# Power_supply.net
KiCad netlist of a schematic drawn in EAGLE
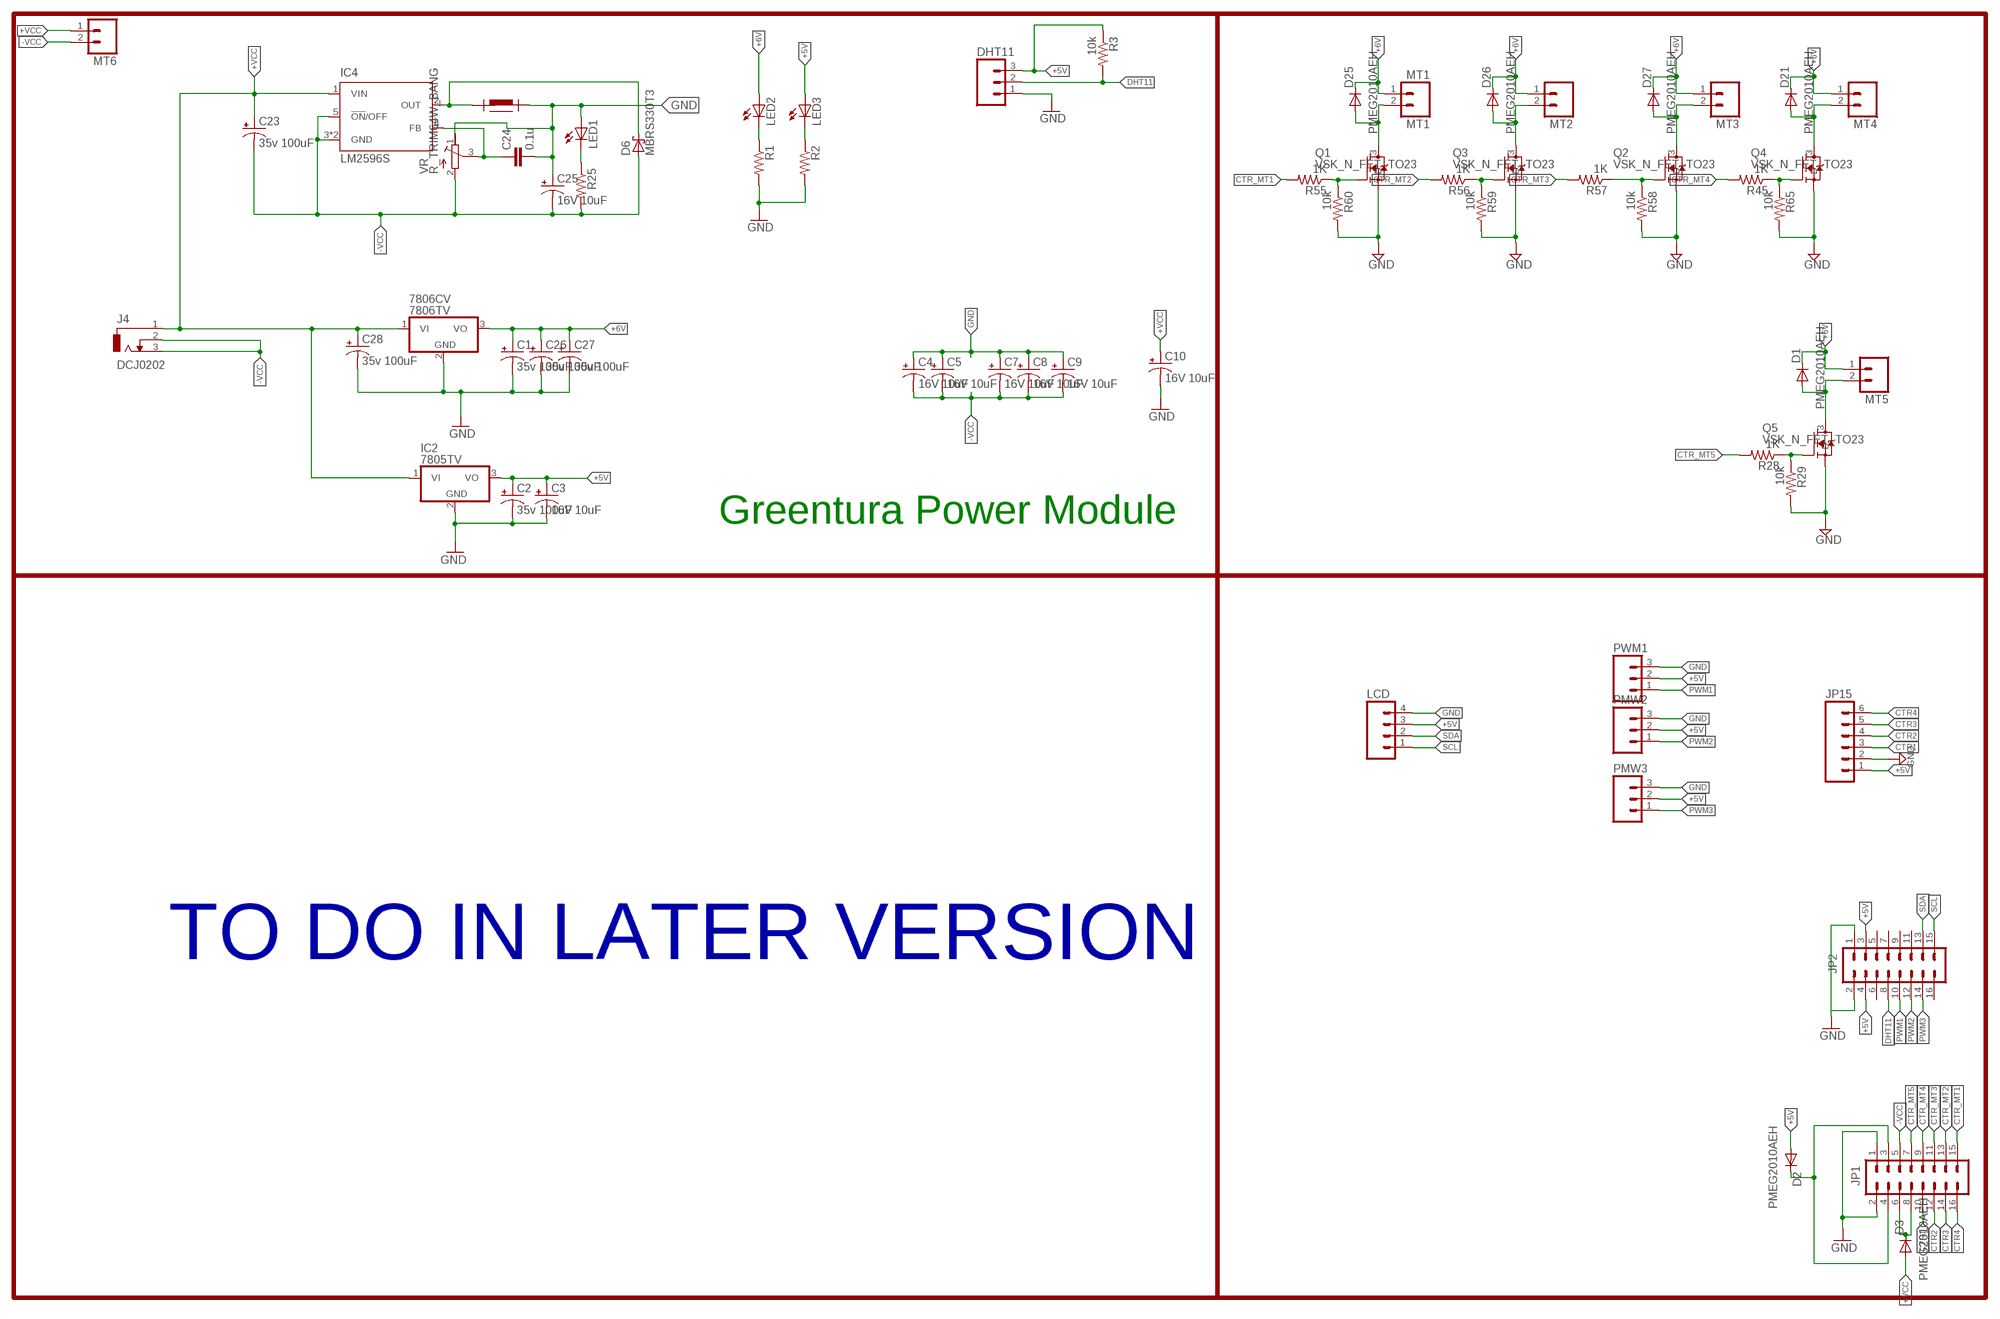
[diagram p0: schematic, sheet 1]

(export (version "E")
  (design (tool "Eeschema 10.0.6"))
  (components
    (comp (ref "7806CV")
      (value "7806TV")
      (footprint "eagle-import:TO220V")
      (libsource (lib "eagle-import") (part "78TV05"))
    )
    (comp (ref "C1")
      (value "35v 100uF")
      (footprint "eagle-import:TT5D9")
      (libsource (lib "eagle-import") (part "CPOL-USTT5D9"))
    )
    (comp (ref "C2")
      (value "35v 100uF")
      (footprint "eagle-import:UD-8X10_NICHICON")
      (libsource (lib "eagle-import") (part "CPOL-USUD-8X10"))
    )
    (comp (ref "C3")
      (value "16V 10uF")
      (footprint "eagle-import:SMC_D")
      (libsource (lib "eagle-import") (part "CPOL-USSMCD"))
    )
    (comp (ref "C4")
      (value "16V 10uF")
      (footprint "eagle-import:TT2D6")
      (libsource (lib "eagle-import") (part "CPOL-USTT2D6"))
    )
    (comp (ref "C5")
      (value "16V 10uF")
      (footprint "eagle-import:TT2D6")
      (libsource (lib "eagle-import") (part "CPOL-USTT2D6"))
    )
    (comp (ref "C7")
      (value "16V 10uF")
      (footprint "eagle-import:TT2D6")
      (libsource (lib "eagle-import") (part "CPOL-USTT2D6"))
    )
    (comp (ref "C8")
      (value "16V 10uF")
      (footprint "eagle-import:TT2D6")
      (libsource (lib "eagle-import") (part "CPOL-USTT2D6"))
    )
    (comp (ref "C9")
      (value "16V 10uF")
      (footprint "eagle-import:TT2D6")
      (libsource (lib "eagle-import") (part "CPOL-USTT2D6"))
    )
    (comp (ref "C10")
      (value "16V 10uF")
      (footprint "eagle-import:UD-6,3X7,7_NICHICON")
      (libsource (lib "eagle-import") (part "CPOL-USUD-6,3X7,7"))
    )
    (comp (ref "C23")
      (value "35v 100uF")
      (footprint "eagle-import:UD-6,3X7,7_NICHICON")
      (libsource (lib "eagle-import") (part "CPOL-USUD-6,3X7,7"))
    )
    (comp (ref "C24")
      (value "0.1u")
      (footprint "eagle-import:SPARKFUN_0603-CAP")
      (libsource (lib "eagle-import") (part "SPARKFUN_CAP0603-CAP"))
    )
    (comp (ref "C25")
      (value "16V 10uF")
      (footprint "eagle-import:UD-8X10_NICHICON")
      (libsource (lib "eagle-import") (part "CPOL-USUD-8X10"))
    )
    (comp (ref "C26")
      (value "35v 100uF")
      (footprint "eagle-import:TT5D9")
      (libsource (lib "eagle-import") (part "CPOL-USTT5D9"))
    )
    (comp (ref "C27")
      (value "35v 100uF")
      (footprint "eagle-import:TT5D9")
      (libsource (lib "eagle-import") (part "CPOL-USTT5D9"))
    )
    (comp (ref "C28")
      (value "35v 100uF")
      (footprint "eagle-import:SMC_C")
      (libsource (lib "eagle-import") (part "CPOL-USSMCC"))
    )
    (comp (ref "D1")
      (value "PMEG2010AEH")
      (footprint "eagle-import:SOT123F")
      (fields (field (name "PARTNO") "PMEG2010AEH,115"))
      (libsource (lib "eagle-import") (part "DIOD_SOT123F"))
    )
    (comp (ref "D2")
      (value "PMEG2010AEH")
      (footprint "eagle-import:SOT123F")
      (fields (field (name "PARTNO") "PMEG2010AEH,115"))
      (libsource (lib "eagle-import") (part "DIOD_SOT123F"))
    )
    (comp (ref "D3")
      (value "PMEG2010AEH")
      (footprint "eagle-import:SOT123F")
      (fields (field (name "PARTNO") "PMEG2010AEH,115"))
      (libsource (lib "eagle-import") (part "DIOD_SOT123F"))
    )
    (comp (ref "D6")
      (value "MBRS330T3")
      (footprint "eagle-import:SMC")
      (libsource (lib "eagle-import") (part "MBRS30T33"))
    )
    (comp (ref "D21")
      (value "PMEG2010AEH")
      (footprint "eagle-import:SOT123F")
      (fields (field (name "PARTNO") "PMEG2010AEH,115"))
      (libsource (lib "eagle-import") (part "DIOD_SOT123F"))
    )
    (comp (ref "D25")
      (value "PMEG2010AEH")
      (footprint "eagle-import:SOT123F")
      (fields (field (name "PARTNO") "PMEG2010AEH,115"))
      (libsource (lib "eagle-import") (part "DIOD_SOT123F"))
    )
    (comp (ref "D26")
      (value "PMEG2010AEH")
      (footprint "eagle-import:SOT123F")
      (fields (field (name "PARTNO") "PMEG2010AEH,115"))
      (libsource (lib "eagle-import") (part "DIOD_SOT123F"))
    )
    (comp (ref "D27")
      (value "PMEG2010AEH")
      (footprint "eagle-import:SOT123F")
      (fields (field (name "PARTNO") "PMEG2010AEH,115"))
      (libsource (lib "eagle-import") (part "DIOD_SOT123F"))
    )
    (comp (ref "DHT11")
      (value "M03PTH")
      (footprint "eagle-import:1X03")
      (libsource (lib "eagle-import") (part "M03PTH"))
    )
    (comp (ref "IC2")
      (value "7805TV")
      (footprint "eagle-import:TO220V")
      (libsource (lib "eagle-import") (part "78TV05"))
    )
    (comp (ref "IC4")
      (value "LM2596S")
      (footprint "eagle-import:TO263-5")
      (fields (field (name "MF") "NATIONAL SEMICONDUCTOR") (field (name "MPN") "LM2596S-ADJ/NOPB"))
      (libsource (lib "eagle-import") (part "LM2596S"))
    )
    (comp (ref "J4")
      (value "DCJ0202")
      (footprint "eagle-import:DCJ0202")
      (libsource (lib "eagle-import") (part "DCJ0202"))
    )
    (comp (ref "JP1")
      (value "M08X2")
      (footprint "eagle-import:2X8")
      (libsource (lib "eagle-import") (part "M08X2"))
    )
    (comp (ref "JP2")
      (value "M08X2")
      (footprint "eagle-import:2X8")
      (libsource (lib "eagle-import") (part "M08X2"))
    )
    (comp (ref "JP15")
      (value "M06POLAR")
      (footprint "eagle-import:MOLEX-1X6")
      (libsource (lib "eagle-import") (part "M06POLAR"))
    )
    (comp (ref "LCD")
      (value "M04PTH")
      (footprint "eagle-import:1X04")
      (libsource (lib "eagle-import") (part "M04PTH"))
    )
    (comp (ref "LED1")
      (value "SPARKFUN_LED0603")
      (footprint "eagle-import:SPARKFUN_LED-0603")
      (libsource (lib "eagle-import") (part "SPARKFUN_LED0603"))
    )
    (comp (ref "LED2")
      (value "SPARKFUN_LED0603")
      (footprint "eagle-import:SPARKFUN_LED-0603")
      (libsource (lib "eagle-import") (part "SPARKFUN_LED0603"))
    )
    (comp (ref "LED3")
      (value "SPARKFUN_LED0603")
      (footprint "eagle-import:SPARKFUN_LED-0603")
      (libsource (lib "eagle-import") (part "SPARKFUN_LED0603"))
    )
    (comp (ref "MT1")
      (value "MT1")
      (footprint "eagle-import:MOLEX-1X2")
      (libsource (lib "eagle-import") (part "M02POLAR"))
    )
    (comp (ref "MT2")
      (value "M02POLAR")
      (footprint "eagle-import:MOLEX-1X2")
      (libsource (lib "eagle-import") (part "M02POLAR"))
    )
    (comp (ref "MT3")
      (value "M02POLAR")
      (footprint "eagle-import:MOLEX-1X2")
      (libsource (lib "eagle-import") (part "M02POLAR"))
    )
    (comp (ref "MT4")
      (value "M02POLAR")
      (footprint "eagle-import:MOLEX-1X2")
      (libsource (lib "eagle-import") (part "M02POLAR"))
    )
    (comp (ref "MT5")
      (value "M02POLAR")
      (footprint "eagle-import:MOLEX-1X2")
      (libsource (lib "eagle-import") (part "M02POLAR"))
    )
    (comp (ref "MT6")
      (value "M025MM")
      (footprint "eagle-import:SCREWTERMINAL-5MM-2")
      (libsource (lib "eagle-import") (part "M025MM"))
    )
    (comp (ref "PMW2")
      (value "M03PTH")
      (footprint "eagle-import:1X03")
      (libsource (lib "eagle-import") (part "M03PTH"))
    )
    (comp (ref "PMW3")
      (value "M03PTH")
      (footprint "eagle-import:1X03")
      (libsource (lib "eagle-import") (part "M03PTH"))
    )
    (comp (ref "PWM1")
      (value "M03PTH")
      (footprint "eagle-import:1X03")
      (libsource (lib "eagle-import") (part "M03PTH"))
    )
    (comp (ref "Q1")
      (value "VSK_N_FET_TO23")
      (footprint "eagle-import:SOT23")
      (libsource (lib "eagle-import") (part "VSK_N_FET_TO23"))
    )
    (comp (ref "Q2")
      (value "VSK_N_FET_TO23")
      (footprint "eagle-import:SOT23")
      (libsource (lib "eagle-import") (part "VSK_N_FET_TO23"))
    )
    (comp (ref "Q3")
      (value "VSK_N_FET_TO23")
      (footprint "eagle-import:SOT23")
      (libsource (lib "eagle-import") (part "VSK_N_FET_TO23"))
    )
    (comp (ref "Q4")
      (value "VSK_N_FET_TO23")
      (footprint "eagle-import:SOT23")
      (libsource (lib "eagle-import") (part "VSK_N_FET_TO23"))
    )
    (comp (ref "Q5")
      (value "VSK_N_FET_TO23")
      (footprint "eagle-import:SOT23")
      (libsource (lib "eagle-import") (part "VSK_N_FET_TO23"))
    )
    (comp (ref "R1")
      (value "SPARKFUN_RESISTOR0805-RES")
      (footprint "eagle-import:SPARKFUN_0805")
      (libsource (lib "eagle-import") (part "SPARKFUN_RESISTOR0805-RES"))
    )
    (comp (ref "R2")
      (value "SPARKFUN_RESISTOR0805-RES")
      (footprint "eagle-import:SPARKFUN_0805")
      (libsource (lib "eagle-import") (part "SPARKFUN_RESISTOR0805-RES"))
    )
    (comp (ref "R3")
      (value "10k")
      (footprint "eagle-import:R0603")
      (libsource (lib "eagle-import") (part "R-US_R0603"))
    )
    (comp (ref "R25")
      (value "SPARKFUN_RESISTOR0805-RES")
      (footprint "eagle-import:SPARKFUN_0805")
      (libsource (lib "eagle-import") (part "SPARKFUN_RESISTOR0805-RES"))
    )
    (comp (ref "R28")
      (value "1K")
      (footprint "eagle-import:R0603")
      (libsource (lib "eagle-import") (part "R-US_R0603"))
    )
    (comp (ref "R29")
      (value "10k")
      (footprint "eagle-import:R0603")
      (libsource (lib "eagle-import") (part "R-US_R0603"))
    )
    (comp (ref "R45")
      (value "1K")
      (footprint "eagle-import:R0603")
      (libsource (lib "eagle-import") (part "R-US_R0603"))
    )
    (comp (ref "R55")
      (value "1K")
      (footprint "eagle-import:R0603")
      (libsource (lib "eagle-import") (part "R-US_R0603"))
    )
    (comp (ref "R56")
      (value "1K")
      (footprint "eagle-import:R0603")
      (libsource (lib "eagle-import") (part "R-US_R0603"))
    )
    (comp (ref "R57")
      (value "1K")
      (footprint "eagle-import:R0603")
      (libsource (lib "eagle-import") (part "R-US_R0603"))
    )
    (comp (ref "R58")
      (value "10k")
      (footprint "eagle-import:R0603")
      (libsource (lib "eagle-import") (part "R-US_R0603"))
    )
    (comp (ref "R59")
      (value "10k")
      (footprint "eagle-import:R0603")
      (libsource (lib "eagle-import") (part "R-US_R0603"))
    )
    (comp (ref "R60")
      (value "10k")
      (footprint "eagle-import:R0603")
      (libsource (lib "eagle-import") (part "R-US_R0603"))
    )
    (comp (ref "R65")
      (value "10k")
      (footprint "eagle-import:R0603")
      (libsource (lib "eagle-import") (part "R-US_R0603"))
    )
    (comp (ref "U$2")
      (value "BIG_INDUCTOR")
      (footprint "eagle-import:12X12")
      (libsource (lib "eagle-import") (part "BIG_INDUCTOR"))
    )
    (comp (ref "VR")
      (value "R_TRIM64W_BANG")
      (footprint "eagle-import:RTRIM64W_BANG")
      (libsource (lib "eagle-import") (part "R_TRIM64W_BANG"))
    )
  )
  (nets
    (net (code "1") (name "+5V") (class "Default")
      (node (ref "C2") (pin "+") (pinfunction "+_+") (pintype "passive"))
      (node (ref "C3") (pin "+") (pinfunction "+_+") (pintype "passive"))
      (node (ref "D2") (pin "A") (pinfunction "A_A") (pintype "passive"))
      (node (ref "DHT11") (pin "3") (pinfunction "3_3") (pintype "passive"))
      (node (ref "IC2") (pin "3") (pinfunction "VO_3") (pintype "passive"))
      (node (ref "JP15") (pin "1") (pinfunction "1_1") (pintype "passive"))
      (node (ref "JP2") (pin "3") (pinfunction "3_3") (pintype "passive"))
      (node (ref "JP2") (pin "4") (pinfunction "4_4") (pintype "passive"))
      (node (ref "LCD") (pin "3") (pinfunction "3_3") (pintype "passive"))
      (node (ref "LED3") (pin "A") (pinfunction "A_A") (pintype "passive"))
      (node (ref "PMW2") (pin "2") (pinfunction "2_2") (pintype "passive"))
      (node (ref "PMW3") (pin "2") (pinfunction "2_2") (pintype "passive"))
      (node (ref "PWM1") (pin "2") (pinfunction "2_2") (pintype "passive"))
      (node (ref "R3") (pin "1") (pinfunction "1_1") (pintype "passive"))
    )
    (net (code "2") (name "+6V") (class "Default")
      (node (ref "7806CV") (pin "3") (pinfunction "VO_3") (pintype "passive"))
      (node (ref "C1") (pin "+") (pinfunction "+_+") (pintype "passive"))
      (node (ref "C26") (pin "+") (pinfunction "+_+") (pintype "passive"))
      (node (ref "C27") (pin "+") (pinfunction "+_+") (pintype "passive"))
      (node (ref "D1") (pin "C") (pinfunction "C_C") (pintype "passive"))
      (node (ref "D21") (pin "C") (pinfunction "C_C") (pintype "passive"))
      (node (ref "D25") (pin "C") (pinfunction "C_C") (pintype "passive"))
      (node (ref "D26") (pin "C") (pinfunction "C_C") (pintype "passive"))
      (node (ref "D27") (pin "C") (pinfunction "C_C") (pintype "passive"))
      (node (ref "LED2") (pin "A") (pinfunction "A_A") (pintype "passive"))
      (node (ref "MT1") (pin "1") (pinfunction "1_1") (pintype "passive"))
      (node (ref "MT2") (pin "1") (pinfunction "1_1") (pintype "passive"))
      (node (ref "MT3") (pin "1") (pinfunction "1_1") (pintype "passive"))
      (node (ref "MT4") (pin "1") (pinfunction "1_1") (pintype "passive"))
      (node (ref "MT5") (pin "1") (pinfunction "1_1") (pintype "passive"))
    )
    (net (code "3") (name "+VCC") (class "Default")
      (node (ref "7806CV") (pin "1") (pinfunction "VI_1") (pintype "input"))
      (node (ref "C10") (pin "+") (pinfunction "+_+") (pintype "passive"))
      (node (ref "C23") (pin "+") (pinfunction "+_+") (pintype "passive"))
      (node (ref "C28") (pin "+") (pinfunction "+_+") (pintype "passive"))
      (node (ref "D3") (pin "A") (pinfunction "A_A") (pintype "passive"))
      (node (ref "IC2") (pin "1") (pinfunction "VI_1") (pintype "input"))
      (node (ref "IC4") (pin "1") (pinfunction "VIN_1") (pintype "input"))
      (node (ref "J4") (pin "1") (pinfunction "1_1") (pintype "passive"))
      (node (ref "MT6") (pin "1") (pinfunction "1_1") (pintype "passive"))
    )
    (net (code "4") (name "-VCC") (class "Default")
      (node (ref "C23") (pin "-") (pinfunction "-_-") (pintype "passive"))
      (node (ref "C25") (pin "-") (pinfunction "-_-") (pintype "passive"))
      (node (ref "C4") (pin "-") (pinfunction "-_-") (pintype "passive"))
      (node (ref "C5") (pin "-") (pinfunction "-_-") (pintype "passive"))
      (node (ref "C7") (pin "-") (pinfunction "-_-") (pintype "passive"))
      (node (ref "C8") (pin "-") (pinfunction "-_-") (pintype "passive"))
      (node (ref "C9") (pin "-") (pinfunction "-_-") (pintype "passive"))
      (node (ref "D6") (pin "A") (pinfunction "A_A") (pintype "passive"))
      (node (ref "IC4") (pin "3") (pinfunction "GND_3") (pintype "power_in"))
      (node (ref "IC4") (pin "5") (pinfunction "~{ON}/OFF_5") (pintype "input"))
      (node (ref "IC4") (pin "6") (pinfunction "GND_6") (pintype "power_in"))
      (node (ref "J4") (pin "2") (pinfunction "2_2") (pintype "passive"))
      (node (ref "J4") (pin "3") (pinfunction "3_3") (pintype "passive"))
      (node (ref "JP1") (pin "5") (pinfunction "5_5") (pintype "passive"))
      (node (ref "MT6") (pin "2") (pinfunction "2_2") (pintype "passive"))
      (node (ref "R25") (pin "2") (pinfunction "2_2") (pintype "passive"))
      (node (ref "VR") (pin "2") (pinfunction "E_2") (pintype "passive"))
    )
    (net (code "5") (name "CTR1") (class "Default")
      (node (ref "JP1") (pin "10") (pinfunction "10_10") (pintype "passive"))
      (node (ref "JP15") (pin "3") (pinfunction "3_3") (pintype "passive"))
    )
    (net (code "6") (name "CTR2") (class "Default")
      (node (ref "JP1") (pin "12") (pinfunction "12_12") (pintype "passive"))
      (node (ref "JP15") (pin "4") (pinfunction "4_4") (pintype "passive"))
    )
    (net (code "7") (name "CTR3") (class "Default")
      (node (ref "JP1") (pin "14") (pinfunction "14_14") (pintype "passive"))
      (node (ref "JP15") (pin "5") (pinfunction "5_5") (pintype "passive"))
    )
    (net (code "8") (name "CTR4") (class "Default")
      (node (ref "JP1") (pin "16") (pinfunction "16_16") (pintype "passive"))
      (node (ref "JP15") (pin "6") (pinfunction "6_6") (pintype "passive"))
    )
    (net (code "9") (name "CTR_MT1") (class "Default")
      (node (ref "JP1") (pin "15") (pinfunction "15_15") (pintype "passive"))
      (node (ref "R55") (pin "2") (pinfunction "2_2") (pintype "passive"))
    )
    (net (code "10") (name "CTR_MT2") (class "Default")
      (node (ref "JP1") (pin "13") (pinfunction "13_13") (pintype "passive"))
      (node (ref "R56") (pin "2") (pinfunction "2_2") (pintype "passive"))
    )
    (net (code "11") (name "CTR_MT3") (class "Default")
      (node (ref "JP1") (pin "11") (pinfunction "11_11") (pintype "passive"))
      (node (ref "R57") (pin "2") (pinfunction "2_2") (pintype "passive"))
    )
    (net (code "12") (name "CTR_MT4") (class "Default")
      (node (ref "JP1") (pin "9") (pinfunction "9_9") (pintype "passive"))
      (node (ref "R45") (pin "2") (pinfunction "2_2") (pintype "passive"))
    )
    (net (code "13") (name "CTR_MT5") (class "Default")
      (node (ref "JP1") (pin "7") (pinfunction "7_7") (pintype "passive"))
      (node (ref "R28") (pin "2") (pinfunction "2_2") (pintype "passive"))
    )
    (net (code "14") (name "DHT11") (class "Default")
      (node (ref "DHT11") (pin "2") (pinfunction "2_2") (pintype "passive"))
      (node (ref "JP2") (pin "8") (pinfunction "8_8") (pintype "passive"))
      (node (ref "R3") (pin "2") (pinfunction "2_2") (pintype "passive"))
    )
    (net (code "15") (name "GND") (class "Default")
      (node (ref "7806CV") (pin "2") (pinfunction "GND_2") (pintype "passive"))
      (node (ref "C1") (pin "-") (pinfunction "-_-") (pintype "passive"))
      (node (ref "C10") (pin "-") (pinfunction "-_-") (pintype "passive"))
      (node (ref "C2") (pin "-") (pinfunction "-_-") (pintype "passive"))
      (node (ref "C24") (pin "2") (pinfunction "2_2") (pintype "passive"))
      (node (ref "C25") (pin "+") (pinfunction "+_+") (pintype "passive"))
      (node (ref "C26") (pin "-") (pinfunction "-_-") (pintype "passive"))
      (node (ref "C27") (pin "-") (pinfunction "-_-") (pintype "passive"))
      (node (ref "C28") (pin "-") (pinfunction "-_-") (pintype "passive"))
      (node (ref "C3") (pin "-") (pinfunction "-_-") (pintype "passive"))
      (node (ref "C4") (pin "+") (pinfunction "+_+") (pintype "passive"))
      (node (ref "C5") (pin "+") (pinfunction "+_+") (pintype "passive"))
      (node (ref "C7") (pin "+") (pinfunction "+_+") (pintype "passive"))
      (node (ref "C8") (pin "+") (pinfunction "+_+") (pintype "passive"))
      (node (ref "C9") (pin "+") (pinfunction "+_+") (pintype "passive"))
      (node (ref "DHT11") (pin "1") (pinfunction "1_1") (pintype "passive"))
      (node (ref "IC2") (pin "2") (pinfunction "GND_2") (pintype "passive"))
      (node (ref "JP1") (pin "1") (pinfunction "1_1") (pintype "passive"))
      (node (ref "JP1") (pin "2") (pinfunction "2_2") (pintype "passive"))
      (node (ref "JP15") (pin "2") (pinfunction "2_2") (pintype "passive"))
      (node (ref "JP2") (pin "1") (pinfunction "1_1") (pintype "passive"))
      (node (ref "JP2") (pin "2") (pinfunction "2_2") (pintype "passive"))
      (node (ref "LCD") (pin "4") (pinfunction "4_4") (pintype "passive"))
      (node (ref "LED1") (pin "A") (pinfunction "A_A") (pintype "passive"))
      (node (ref "PMW2") (pin "3") (pinfunction "3_3") (pintype "passive"))
      (node (ref "PMW3") (pin "3") (pinfunction "3_3") (pintype "passive"))
      (node (ref "PWM1") (pin "3") (pinfunction "3_3") (pintype "passive"))
      (node (ref "Q1") (pin "2") (pinfunction "S_2") (pintype "passive"))
      (node (ref "Q2") (pin "2") (pinfunction "S_2") (pintype "passive"))
      (node (ref "Q3") (pin "2") (pinfunction "S_2") (pintype "passive"))
      (node (ref "Q4") (pin "2") (pinfunction "S_2") (pintype "passive"))
      (node (ref "Q5") (pin "2") (pinfunction "S_2") (pintype "passive"))
      (node (ref "R1") (pin "2") (pinfunction "2_2") (pintype "passive"))
      (node (ref "R2") (pin "2") (pinfunction "2_2") (pintype "passive"))
      (node (ref "R29") (pin "2") (pinfunction "2_2") (pintype "passive"))
      (node (ref "R58") (pin "2") (pinfunction "2_2") (pintype "passive"))
      (node (ref "R59") (pin "2") (pinfunction "2_2") (pintype "passive"))
      (node (ref "R60") (pin "2") (pinfunction "2_2") (pintype "passive"))
      (node (ref "R65") (pin "2") (pinfunction "2_2") (pintype "passive"))
      (node (ref "U$2") (pin "P$1") (pinfunction "P$1_P$1") (pintype "bidirectional"))
      (node (ref "VR") (pin "1") (pinfunction "A_1") (pintype "passive"))
    )
    (net (code "16") (name "Net-(D2-PadC)") (class "Default")
      (node (ref "D2") (pin "C") (pinfunction "C_C") (pintype "passive"))
      (node (ref "JP1") (pin "3") (pinfunction "3_3") (pintype "passive"))
      (node (ref "JP1") (pin "4") (pinfunction "4_4") (pintype "passive"))
    )
    (net (code "17") (name "Net-(D3-PadC)") (class "Default")
      (node (ref "D3") (pin "C") (pinfunction "C_C") (pintype "passive"))
      (node (ref "JP1") (pin "6") (pinfunction "6_6") (pintype "passive"))
      (node (ref "JP1") (pin "8") (pinfunction "8_8") (pintype "passive"))
    )
    (net (code "18") (name "Net-(IC4-FB)") (class "Default")
      (node (ref "C24") (pin "1") (pinfunction "1_1") (pintype "passive"))
      (node (ref "IC4") (pin "4") (pinfunction "FB_4") (pintype "input"))
      (node (ref "VR") (pin "3") (pinfunction "S_3") (pintype "passive"))
    )
    (net (code "19") (name "Net-(IC4-OUT)") (class "Default")
      (node (ref "D6") (pin "C") (pinfunction "C_C") (pintype "passive"))
      (node (ref "IC4") (pin "2") (pinfunction "OUT_2") (pintype "output"))
      (node (ref "U$2") (pin "P$2") (pinfunction "P$2_P$2") (pintype "bidirectional"))
    )
    (net (code "20") (name "Net-(LED1-PadC)") (class "Default")
      (node (ref "LED1") (pin "C") (pinfunction "C_C") (pintype "passive"))
      (node (ref "R25") (pin "1") (pinfunction "1_1") (pintype "passive"))
    )
    (net (code "21") (name "Net-(LED2-PadC)") (class "Default")
      (node (ref "LED2") (pin "C") (pinfunction "C_C") (pintype "passive"))
      (node (ref "R1") (pin "1") (pinfunction "1_1") (pintype "passive"))
    )
    (net (code "22") (name "Net-(LED3-PadC)") (class "Default")
      (node (ref "LED3") (pin "C") (pinfunction "C_C") (pintype "passive"))
      (node (ref "R2") (pin "1") (pinfunction "1_1") (pintype "passive"))
    )
    (net (code "23") (name "Net-(Q1-D)") (class "Default")
      (node (ref "D25") (pin "A") (pinfunction "A_A") (pintype "passive"))
      (node (ref "MT1") (pin "2") (pinfunction "2_2") (pintype "passive"))
      (node (ref "Q1") (pin "3") (pinfunction "D_3") (pintype "passive"))
    )
    (net (code "24") (name "Net-(Q1-G)") (class "Default")
      (node (ref "Q1") (pin "1") (pinfunction "G_1") (pintype "passive"))
      (node (ref "R55") (pin "1") (pinfunction "1_1") (pintype "passive"))
      (node (ref "R60") (pin "1") (pinfunction "1_1") (pintype "passive"))
    )
    (net (code "25") (name "Net-(Q2-D)") (class "Default")
      (node (ref "D27") (pin "A") (pinfunction "A_A") (pintype "passive"))
      (node (ref "MT3") (pin "2") (pinfunction "2_2") (pintype "passive"))
      (node (ref "Q2") (pin "3") (pinfunction "D_3") (pintype "passive"))
    )
    (net (code "26") (name "Net-(Q2-G)") (class "Default")
      (node (ref "Q2") (pin "1") (pinfunction "G_1") (pintype "passive"))
      (node (ref "R57") (pin "1") (pinfunction "1_1") (pintype "passive"))
      (node (ref "R58") (pin "1") (pinfunction "1_1") (pintype "passive"))
    )
    (net (code "27") (name "Net-(Q3-D)") (class "Default")
      (node (ref "D26") (pin "A") (pinfunction "A_A") (pintype "passive"))
      (node (ref "MT2") (pin "2") (pinfunction "2_2") (pintype "passive"))
      (node (ref "Q3") (pin "3") (pinfunction "D_3") (pintype "passive"))
    )
    (net (code "28") (name "Net-(Q3-G)") (class "Default")
      (node (ref "Q3") (pin "1") (pinfunction "G_1") (pintype "passive"))
      (node (ref "R56") (pin "1") (pinfunction "1_1") (pintype "passive"))
      (node (ref "R59") (pin "1") (pinfunction "1_1") (pintype "passive"))
    )
    (net (code "29") (name "Net-(Q4-D)") (class "Default")
      (node (ref "D21") (pin "A") (pinfunction "A_A") (pintype "passive"))
      (node (ref "MT4") (pin "2") (pinfunction "2_2") (pintype "passive"))
      (node (ref "Q4") (pin "3") (pinfunction "D_3") (pintype "passive"))
    )
    (net (code "30") (name "Net-(Q4-G)") (class "Default")
      (node (ref "Q4") (pin "1") (pinfunction "G_1") (pintype "passive"))
      (node (ref "R45") (pin "1") (pinfunction "1_1") (pintype "passive"))
      (node (ref "R65") (pin "1") (pinfunction "1_1") (pintype "passive"))
    )
    (net (code "31") (name "Net-(Q5-D)") (class "Default")
      (node (ref "D1") (pin "A") (pinfunction "A_A") (pintype "passive"))
      (node (ref "MT5") (pin "2") (pinfunction "2_2") (pintype "passive"))
      (node (ref "Q5") (pin "3") (pinfunction "D_3") (pintype "passive"))
    )
    (net (code "32") (name "Net-(Q5-G)") (class "Default")
      (node (ref "Q5") (pin "1") (pinfunction "G_1") (pintype "passive"))
      (node (ref "R28") (pin "1") (pinfunction "1_1") (pintype "passive"))
      (node (ref "R29") (pin "1") (pinfunction "1_1") (pintype "passive"))
    )
    (net (code "33") (name "PWM1") (class "Default")
      (node (ref "JP2") (pin "10") (pinfunction "10_10") (pintype "passive"))
      (node (ref "PWM1") (pin "1") (pinfunction "1_1") (pintype "passive"))
    )
    (net (code "34") (name "PWM2") (class "Default")
      (node (ref "JP2") (pin "12") (pinfunction "12_12") (pintype "passive"))
      (node (ref "PMW2") (pin "1") (pinfunction "1_1") (pintype "passive"))
    )
    (net (code "35") (name "PWM3") (class "Default")
      (node (ref "JP2") (pin "14") (pinfunction "14_14") (pintype "passive"))
      (node (ref "PMW3") (pin "1") (pinfunction "1_1") (pintype "passive"))
    )
    (net (code "36") (name "SCL") (class "Default")
      (node (ref "JP2") (pin "15") (pinfunction "15_15") (pintype "passive"))
      (node (ref "LCD") (pin "1") (pinfunction "1_1") (pintype "passive"))
    )
    (net (code "37") (name "SDA") (class "Default")
      (node (ref "JP2") (pin "13") (pinfunction "13_13") (pintype "passive"))
      (node (ref "LCD") (pin "2") (pinfunction "2_2") (pintype "passive"))
    )
    (net (code "38") (name "unconnected-(JP2-Pad5)") (class "Default")
      (node (ref "JP2") (pin "5") (pinfunction "5_5") (pintype "passive"))
    )
    (net (code "39") (name "unconnected-(JP2-Pad6)") (class "Default")
      (node (ref "JP2") (pin "6") (pinfunction "6_6") (pintype "passive"))
    )
    (net (code "40") (name "unconnected-(JP2-Pad7)") (class "Default")
      (node (ref "JP2") (pin "7") (pinfunction "7_7") (pintype "passive"))
    )
    (net (code "41") (name "unconnected-(JP2-Pad9)") (class "Default")
      (node (ref "JP2") (pin "9") (pinfunction "9_9") (pintype "passive"))
    )
    (net (code "42") (name "unconnected-(JP2-Pad11)") (class "Default")
      (node (ref "JP2") (pin "11") (pinfunction "11_11") (pintype "passive"))
    )
    (net (code "43") (name "unconnected-(JP2-Pad16)") (class "Default")
      (node (ref "JP2") (pin "16") (pinfunction "16_16") (pintype "passive"))
    )
  )
)
